# GPRSshield_V2.net
KiCad netlist of a schematic drawn in EAGLE
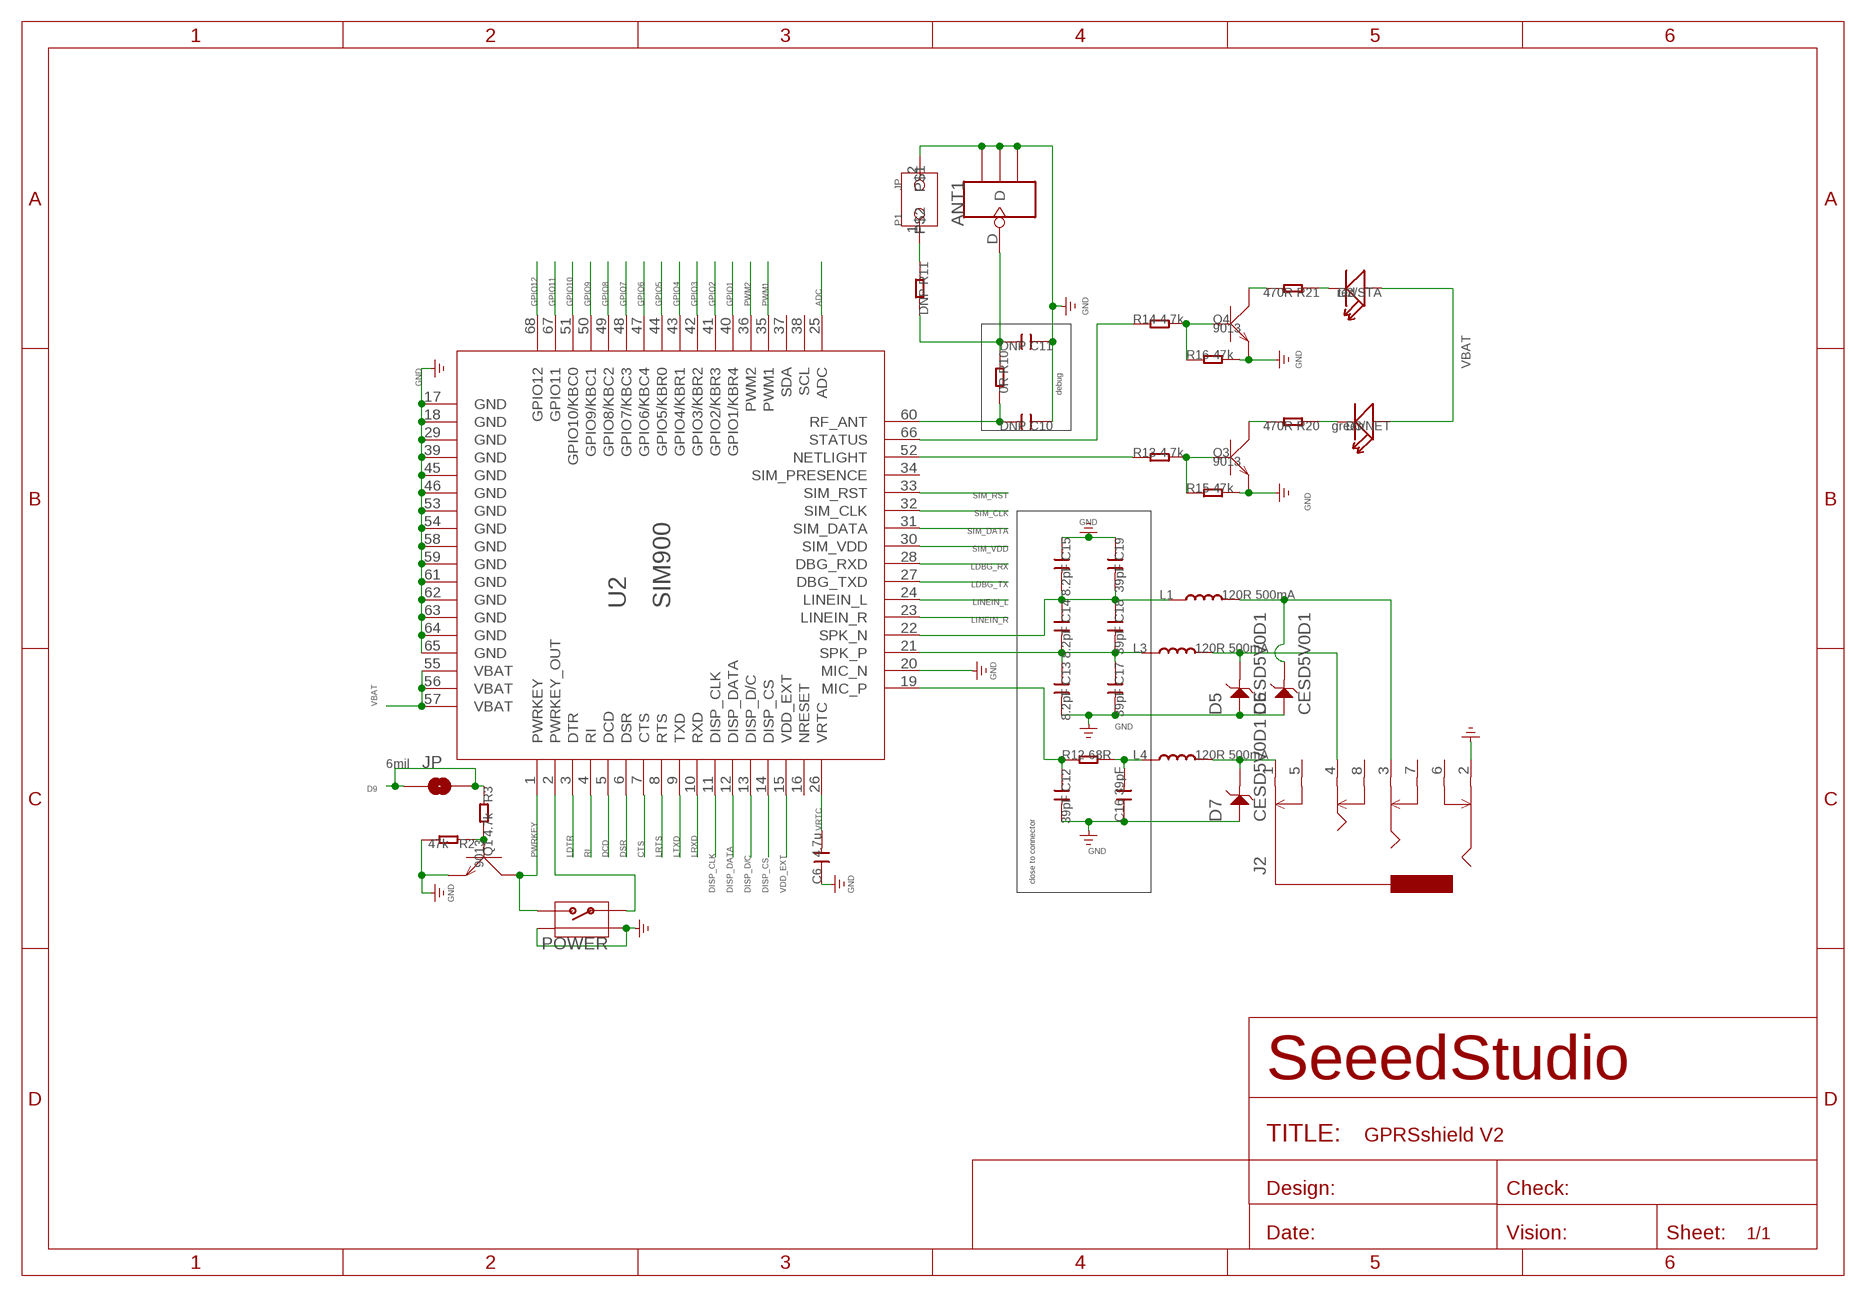
[diagram p0: schematic, sheet 1, part 1 of 2]
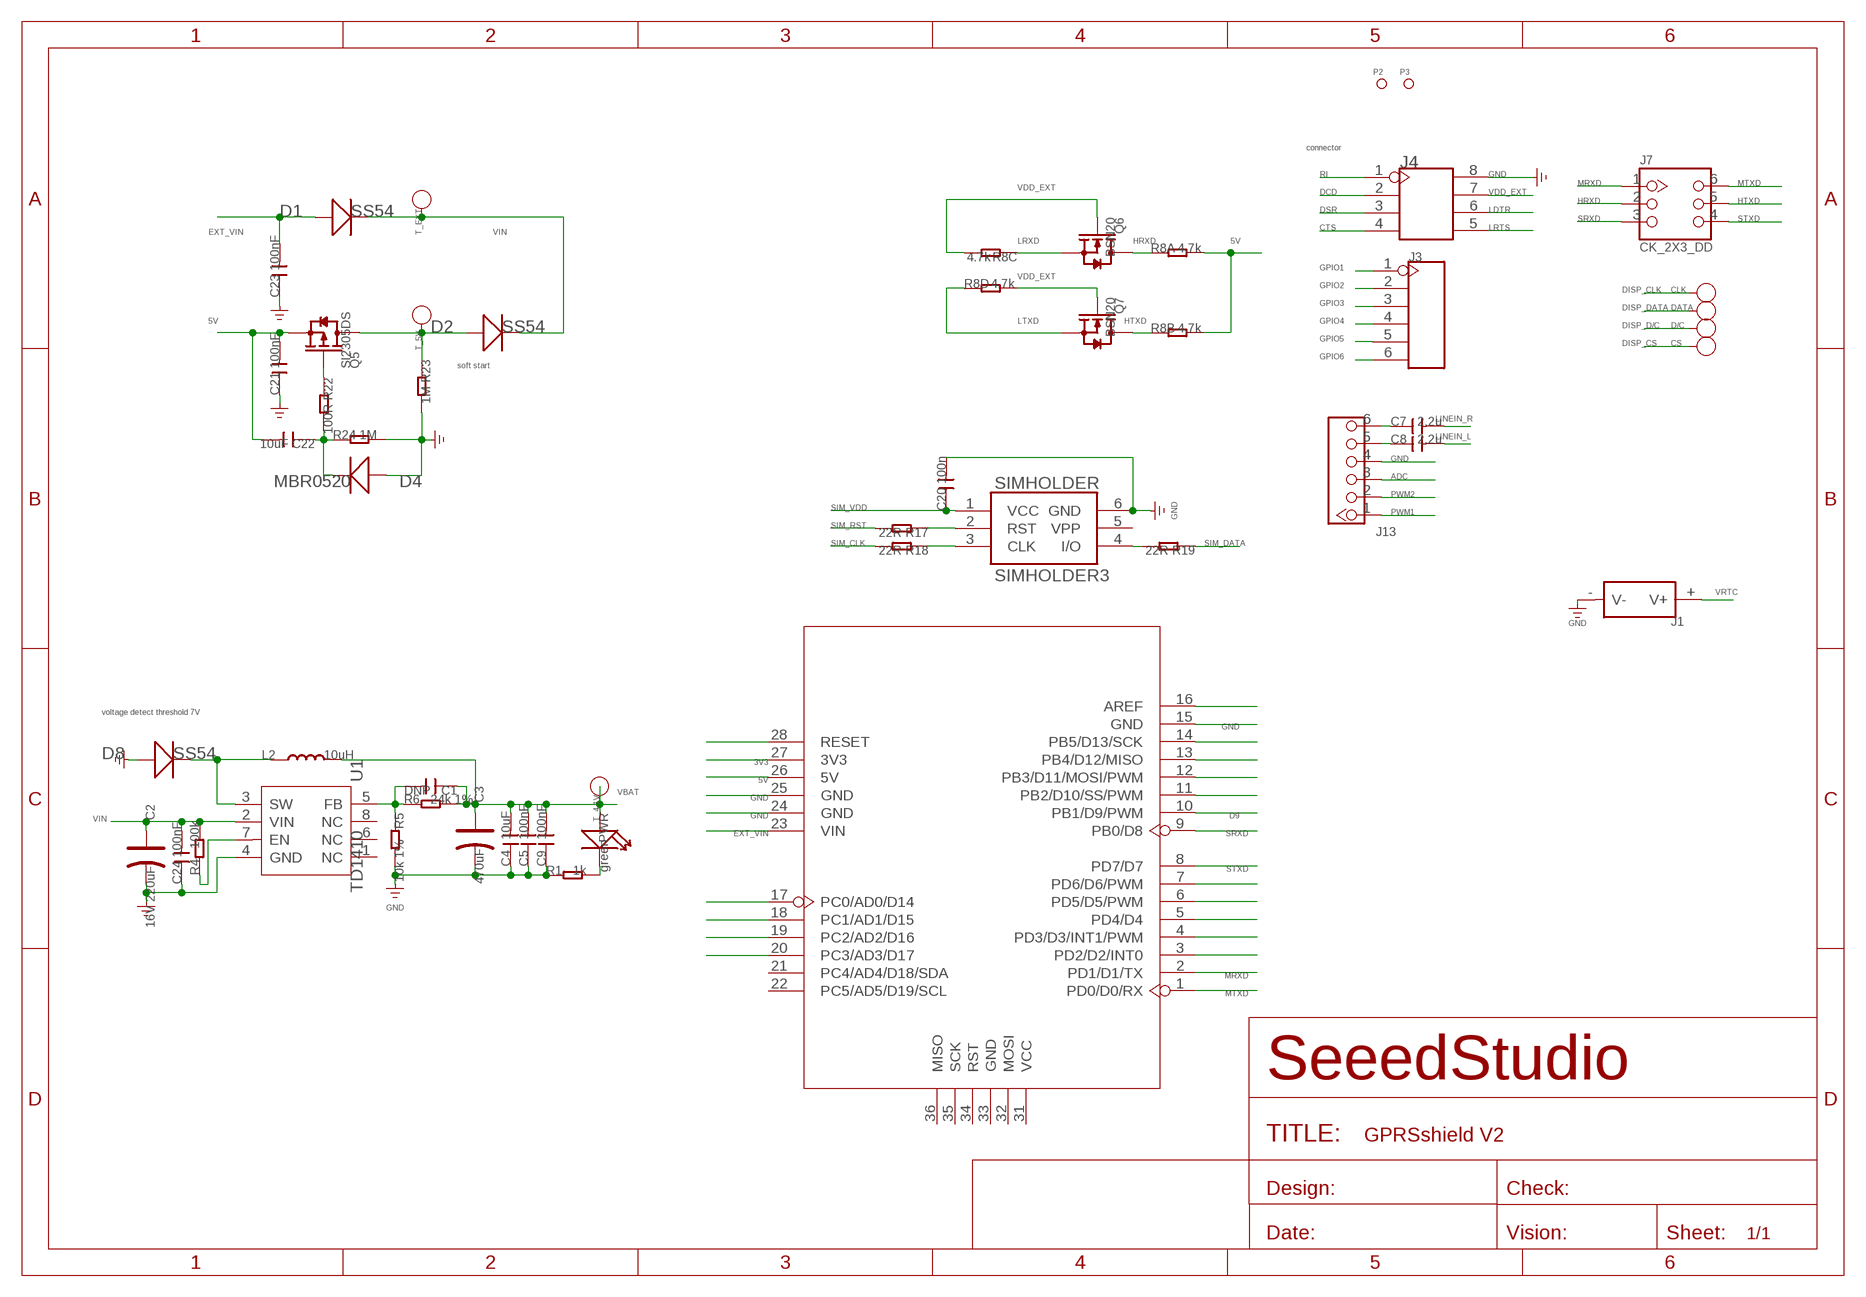
[diagram p1: schematic, sheet 1, part 2 of 2]

(export (version "E")
  (design (tool "Eeschema 10.0.6"))
  (components
    (comp (ref "ANT1")
      (value "ANTENNA-U-FL")
      (footprint "eagle-import:4P-U-FL")
      (libsource (lib "eagle-import") (part "ANTENNA-U-FL"))
    )
    (comp (ref "C1")
      (value "DNP")
      (footprint "eagle-import:C0603")
      (libsource (lib "eagle-import") (part "C-0603"))
    )
    (comp (ref "C2")
      (value "16V 220uF")
      (footprint "eagle-import:ELECTRO-SMD-D-5.6MM")
      (libsource (lib "eagle-import") (part "CAP-ELECTRO-D"))
    )
    (comp (ref "C3")
      (value "470uF")
      (footprint "eagle-import:AVX-D")
      (libsource (lib "eagle-import") (part "CAP-AVX-D"))
    )
    (comp (ref "C4")
      (value "10uF")
      (footprint "eagle-import:C0805")
      (libsource (lib "eagle-import") (part "C-0805"))
    )
    (comp (ref "C5")
      (value "100nF")
      (footprint "eagle-import:C0603")
      (libsource (lib "eagle-import") (part "C-0603"))
    )
    (comp (ref "C6")
      (value "4.7u")
      (footprint "eagle-import:C0805")
      (libsource (lib "eagle-import") (part "C-0805"))
    )
    (comp (ref "C7")
      (value "2.2u")
      (footprint "eagle-import:C0805")
      (libsource (lib "eagle-import") (part "C-0805"))
    )
    (comp (ref "C8")
      (value "2.2u")
      (footprint "eagle-import:C0805")
      (libsource (lib "eagle-import") (part "C-0805"))
    )
    (comp (ref "C9")
      (value "100nF")
      (footprint "eagle-import:C0603")
      (libsource (lib "eagle-import") (part "C-0603"))
    )
    (comp (ref "C10")
      (value "DNP")
      (footprint "eagle-import:C0603")
      (libsource (lib "eagle-import") (part "C-0603"))
    )
    (comp (ref "C11")
      (value "DNP")
      (footprint "eagle-import:C0603")
      (libsource (lib "eagle-import") (part "C-0603"))
    )
    (comp (ref "C12")
      (value "39pF")
      (footprint "eagle-import:C0603")
      (libsource (lib "eagle-import") (part "C-0603"))
    )
    (comp (ref "C13")
      (value "8.2pF")
      (footprint "eagle-import:C0603")
      (libsource (lib "eagle-import") (part "C-0603"))
    )
    (comp (ref "C14")
      (value "8.2pF")
      (footprint "eagle-import:C0603")
      (libsource (lib "eagle-import") (part "C-0603"))
    )
    (comp (ref "C15")
      (value "8.2pF")
      (footprint "eagle-import:C0603")
      (libsource (lib "eagle-import") (part "C-0603"))
    )
    (comp (ref "C16")
      (value "39pF")
      (footprint "eagle-import:C0603")
      (libsource (lib "eagle-import") (part "C-0603"))
    )
    (comp (ref "C17")
      (value "39pF")
      (footprint "eagle-import:C0603")
      (libsource (lib "eagle-import") (part "C-0603"))
    )
    (comp (ref "C18")
      (value "39pF")
      (footprint "eagle-import:C0603")
      (libsource (lib "eagle-import") (part "C-0603"))
    )
    (comp (ref "C19")
      (value "39pF")
      (footprint "eagle-import:C0603")
      (libsource (lib "eagle-import") (part "C-0603"))
    )
    (comp (ref "C20")
      (value "100n")
      (footprint "eagle-import:C0603")
      (libsource (lib "eagle-import") (part "C-0603"))
    )
    (comp (ref "C21")
      (value "100nF")
      (footprint "eagle-import:C0603")
      (libsource (lib "eagle-import") (part "C-0603"))
    )
    (comp (ref "C22")
      (value "10uF")
      (footprint "eagle-import:C0805")
      (libsource (lib "eagle-import") (part "C-0805"))
    )
    (comp (ref "C23")
      (value "100nF")
      (footprint "eagle-import:C0603")
      (libsource (lib "eagle-import") (part "C-0603"))
    )
    (comp (ref "C24")
      (value "100nF")
      (footprint "eagle-import:C0603")
      (libsource (lib "eagle-import") (part "C-0603"))
    )
    (comp (ref "CLK")
      (value "PAD-TEST-POINT-CIRCLE'4545'")
      (footprint "eagle-import:TP_4545")
      (fields (field (name "PARTNO") "DNP"))
      (libsource (lib "eagle-import") (part "PAD-TEST-POINT-CIRCLE'4545'"))
    )
    (comp (ref "CS")
      (value "PAD-TEST-POINT-CIRCLE'4545'")
      (footprint "eagle-import:TP_4545")
      (fields (field (name "PARTNO") "DNP"))
      (libsource (lib "eagle-import") (part "PAD-TEST-POINT-CIRCLE'4545'"))
    )
    (comp (ref "D/C")
      (value "PAD-TEST-POINT-CIRCLE'4545'")
      (footprint "eagle-import:TP_4545")
      (fields (field (name "PARTNO") "DNP"))
      (libsource (lib "eagle-import") (part "PAD-TEST-POINT-CIRCLE'4545'"))
    )
    (comp (ref "D1")
      (value "SS54")
      (footprint "eagle-import:SMB")
      (libsource (lib "eagle-import") (part "D'MBRS240LT3'"))
    )
    (comp (ref "D2")
      (value "SS54")
      (footprint "eagle-import:SMB")
      (libsource (lib "eagle-import") (part "D'MBRS240LT3'"))
    )
    (comp (ref "D2/STA")
      (value "red")
      (footprint "eagle-import:LED-0603")
      (libsource (lib "eagle-import") (part "LED'0603'"))
    )
    (comp (ref "D3/NET")
      (value "green")
      (footprint "eagle-import:LED-0603")
      (libsource (lib "eagle-import") (part "LED'0603'"))
    )
    (comp (ref "D4")
      (value "MBR0520")
      (footprint "eagle-import:SOD123-2.7X1.6")
      (libsource (lib "eagle-import") (part "D'MBR0520LT1'"))
    )
    (comp (ref "D5")
      (value "CESD5V0D1")
      (footprint "eagle-import:SOD123-2.7X1.6")
      (libsource (lib "eagle-import") (part "D-ESD"))
    )
    (comp (ref "D6")
      (value "CESD5V0D1")
      (footprint "eagle-import:SOD123-2.7X1.6")
      (libsource (lib "eagle-import") (part "D-ESD"))
    )
    (comp (ref "D7")
      (value "CESD5V0D1")
      (footprint "eagle-import:SOD123-2.7X1.6")
      (libsource (lib "eagle-import") (part "D-ESD"))
    )
    (comp (ref "D8")
      (value "SS54")
      (footprint "eagle-import:SMB")
      (libsource (lib "eagle-import") (part "D'MBRS240LT3'"))
    )
    (comp (ref "DATA")
      (value "PAD-TEST-POINT-CIRCLE'4545'")
      (footprint "eagle-import:TP_4545")
      (fields (field (name "PARTNO") "DNP"))
      (libsource (lib "eagle-import") (part "PAD-TEST-POINT-CIRCLE'4545'"))
    )
    (comp (ref "J1")
      (value "HOLDER-BAT")
      (footprint "eagle-import:SMD-CR1220-2")
      (libsource (lib "eagle-import") (part "HOLDER-BAT"))
    )
    (comp (ref "J2")
      (value "AUDIO-8P'PJ-3536-L6S'")
      (footprint "eagle-import:8P-3.5-SMD")
      (libsource (lib "eagle-import") (part "AUDIO-8P'PJ-3536-L6S'"))
    )
    (comp (ref "J3")
      (value "HEADER-6P-65/35MIL")
      (footprint "eagle-import:6P-2.54-65_35MIL")
      (libsource (lib "eagle-import") (part "HEADER-6P-65/35MIL"))
    )
    (comp (ref "J4")
      (value "HEADER-2X4P-2.54")
      (footprint "eagle-import:2X4P-2.54")
      (libsource (lib "eagle-import") (part "HEADER-2X4P-2.54"))
    )
    (comp (ref "J7")
      (value "CK_2X3_DD")
      (footprint "eagle-import:CK_2X3")
      (libsource (lib "eagle-import") (part "CK_2X3_DD"))
    )
    (comp (ref "J13")
      (value "HEADER_1X6")
      (footprint "eagle-import:CK_1X6")
      (libsource (lib "eagle-import") (part "HEADER_1X6"))
    )
    (comp (ref "JP")
      (value "PAD-SOLDERJUMPERNC")
      (footprint "eagle-import:2P-SMD-3.3X2")
      (libsource (lib "eagle-import") (part "PAD-SOLDERJUMPERNC"))
    )
    (comp (ref "L1")
      (value "120R 500mA")
      (footprint "eagle-import:L0603")
      (libsource (lib "eagle-import") (part "L'0603'"))
    )
    (comp (ref "L2")
      (value "10uH")
      (footprint "eagle-import:L0630")
      (libsource (lib "eagle-import") (part "L'0630'"))
    )
    (comp (ref "L3")
      (value "120R 500mA")
      (footprint "eagle-import:L0603")
      (libsource (lib "eagle-import") (part "L'0603'"))
    )
    (comp (ref "L4")
      (value "120R 500mA")
      (footprint "eagle-import:L0603")
      (libsource (lib "eagle-import") (part "L'0603'"))
    )
    (comp (ref "P1") (value "JP") (footprint "eagle-import:JP") (libsource (lib "eagle-import") (part "JP")))
    (comp (ref "P2")
      (value "PAD-MARK")
      (footprint "eagle-import:ROUND-MARK-1.0")
      (fields (field (name "PARTNO") "DNP"))
      (libsource (lib "eagle-import") (part "PAD-MARK"))
    )
    (comp (ref "P3")
      (value "PAD-MARK")
      (footprint "eagle-import:ROUND-MARK-1.0")
      (fields (field (name "PARTNO") "DNP"))
      (libsource (lib "eagle-import") (part "PAD-MARK"))
    )
    (comp (ref "POWER")
      (value "BUTTON-4P-REINFORCE'TS-118E'")
      (footprint "eagle-import:4P-SMD-7X3.5X3.5H")
      (libsource (lib "eagle-import") (part "BUTTON-4P-REINFORCE'TS-118E'"))
    )
    (comp (ref "PWR")
      (value "green")
      (footprint "eagle-import:D0603")
      (libsource (lib "eagle-import") (part "007-LED0603"))
    )
    (comp (ref "Q1")
      (value "9013")
      (footprint "eagle-import:SOT23")
      (libsource (lib "eagle-import") (part "TRANSISTOR-NPN-SOT23"))
    )
    (comp (ref "Q3")
      (value "9013")
      (footprint "eagle-import:SOT23")
      (libsource (lib "eagle-import") (part "TRANSISTOR-NPN-SOT23"))
    )
    (comp (ref "Q4")
      (value "9013")
      (footprint "eagle-import:SOT23")
      (libsource (lib "eagle-import") (part "TRANSISTOR-NPN-SOT23"))
    )
    (comp (ref "Q5")
      (value "SI2305DS")
      (footprint "eagle-import:SOT23")
      (libsource (lib "eagle-import") (part "MOSFET-P'SI2323CDS/SI2305DS{lt}BR{gt}'"))
    )
    (comp (ref "Q6")
      (value "BSN20")
      (footprint "eagle-import:SOT23")
      (libsource (lib "eagle-import") (part "MOSFET-N'SOT23'"))
    )
    (comp (ref "Q7")
      (value "BSN20")
      (footprint "eagle-import:SOT23")
      (libsource (lib "eagle-import") (part "MOSFET-N'SOT23'"))
    )
    (comp (ref "R1")
      (value "1k")
      (footprint "eagle-import:R0603")
      (libsource (lib "eagle-import") (part "R-0603"))
    )
    (comp (ref "R2")
      (value "47k")
      (footprint "eagle-import:R0603")
      (libsource (lib "eagle-import") (part "R-0603"))
    )
    (comp (ref "R3")
      (value "4.7k")
      (footprint "eagle-import:R0603")
      (libsource (lib "eagle-import") (part "R-0603"))
    )
    (comp (ref "R4")
      (value "100k")
      (footprint "eagle-import:R0603")
      (libsource (lib "eagle-import") (part "R-0603"))
    )
    (comp (ref "R5")
      (value "10k 1%")
      (footprint "eagle-import:R0603")
      (libsource (lib "eagle-import") (part "R-0603"))
    )
    (comp (ref "R6")
      (value "24k 1%")
      (footprint "eagle-import:R0603")
      (libsource (lib "eagle-import") (part "R-0603"))
    )
    (comp (ref "R8")
      (value "4.7k")
      (footprint "eagle-import:1206-8-3.3X2.4")
      (libsource (lib "eagle-import") (part "R-4R-1206"))
    )
    (comp (ref "R10")
      (value "0R")
      (footprint "eagle-import:R0603")
      (libsource (lib "eagle-import") (part "R-0603"))
    )
    (comp (ref "R11")
      (value "DNP")
      (footprint "eagle-import:R0603")
      (libsource (lib "eagle-import") (part "R-0603"))
    )
    (comp (ref "R12")
      (value "68R")
      (footprint "eagle-import:R0603")
      (libsource (lib "eagle-import") (part "R-0603"))
    )
    (comp (ref "R13")
      (value "4.7k")
      (footprint "eagle-import:R0603")
      (libsource (lib "eagle-import") (part "R-0603"))
    )
    (comp (ref "R14")
      (value "4.7k")
      (footprint "eagle-import:R0603")
      (libsource (lib "eagle-import") (part "R-0603"))
    )
    (comp (ref "R15")
      (value "47k")
      (footprint "eagle-import:R0603")
      (libsource (lib "eagle-import") (part "R-0603"))
    )
    (comp (ref "R16")
      (value "47k")
      (footprint "eagle-import:R0603")
      (libsource (lib "eagle-import") (part "R-0603"))
    )
    (comp (ref "R17")
      (value "22R")
      (footprint "eagle-import:R0603")
      (libsource (lib "eagle-import") (part "R-0603"))
    )
    (comp (ref "R18")
      (value "22R")
      (footprint "eagle-import:R0603")
      (libsource (lib "eagle-import") (part "R-0603"))
    )
    (comp (ref "R19")
      (value "22R")
      (footprint "eagle-import:R0603")
      (libsource (lib "eagle-import") (part "R-0603"))
    )
    (comp (ref "R20")
      (value "470R")
      (footprint "eagle-import:R0603")
      (libsource (lib "eagle-import") (part "R-0603"))
    )
    (comp (ref "R21")
      (value "470R")
      (footprint "eagle-import:R0603")
      (libsource (lib "eagle-import") (part "R-0603"))
    )
    (comp (ref "R22")
      (value "100R")
      (footprint "eagle-import:R0603")
      (libsource (lib "eagle-import") (part "R-0603"))
    )
    (comp (ref "R23")
      (value "1M")
      (footprint "eagle-import:R0603")
      (libsource (lib "eagle-import") (part "R-0603"))
    )
    (comp (ref "R24")
      (value "1M")
      (footprint "eagle-import:R0603")
      (libsource (lib "eagle-import") (part "R-0603"))
    )
    (comp (ref "SIMHOLDER")
      (value "SIMHOLDER3")
      (footprint "eagle-import:SIMHOLDER3")
      (libsource (lib "eagle-import") (part "SIMHOLDER3"))
    )
    (comp (ref "T_4.1V")
      (value "PAD-TEST-POINT-CIRCLE'4545'")
      (footprint "eagle-import:TP_4545")
      (fields (field (name "PARTNO") "DNP") (field (name "PARTNO_1") "DNP"))
      (libsource (lib "eagle-import") (part "PAD-TEST-POINT-CIRCLE'4545'"))
    )
    (comp (ref "T_5V")
      (value "PAD-TEST-POINT-CIRCLE'4545'")
      (footprint "eagle-import:TP_4545")
      (fields (field (name "PARTNO") "DNP") (field (name "PARTNO_1") "DNP"))
      (libsource (lib "eagle-import") (part "PAD-TEST-POINT-CIRCLE'4545'"))
    )
    (comp (ref "T_EXT")
      (value "PAD-TEST-POINT-CIRCLE'4545'")
      (footprint "eagle-import:TP_4545")
      (fields (field (name "PARTNO") "DNP") (field (name "PARTNO_1") "DNP"))
      (libsource (lib "eagle-import") (part "PAD-TEST-POINT-CIRCLE'4545'"))
    )
    (comp (ref "U1")
      (value "TD1410")
      (footprint "eagle-import:SOP8")
      (libsource (lib "eagle-import") (part "TD1410"))
    )
    (comp (ref "U2")
      (value "SIM900")
      (footprint "eagle-import:SIM900")
      (libsource (lib "eagle-import") (part "SIM900"))
    )
    (comp (ref "U3")
      (value "ARDUINO'W/O-SILK'")
      (footprint "eagle-import:ARDUINO-W_O-SILK")
      (libsource (lib "eagle-import") (part "ARDUINO'W/O-SILK'"))
    )
  )
  (nets
    (net (code "1") (name "/3V3") (class "Default")
      (node (ref "U3") (pin "27") (pinfunction "3V3_27") (pintype "bidirectional"))
    )
    (net (code "2") (name "/5V") (class "Default")
      (node (ref "C21") (pin "2") (pinfunction "2_2") (pintype "passive"))
      (node (ref "C22") (pin "2") (pinfunction "2_2") (pintype "passive"))
      (node (ref "Q5") (pin "2") (pinfunction "S_2") (pintype "passive"))
      (node (ref "R8") (pin "7") (pinfunction "2_7") (pintype "passive"))
      (node (ref "R8") (pin "8") (pinfunction "2_8") (pintype "passive"))
      (node (ref "U3") (pin "26") (pinfunction "5V_26") (pintype "bidirectional"))
    )
    (net (code "3") (name "/ADC") (class "Default")
      (node (ref "J13") (pin "3") (pinfunction "3_3") (pintype "bidirectional"))
      (node (ref "U2") (pin "25") (pinfunction "ADC_25") (pintype "input"))
    )
    (net (code "4") (name "/CTS") (class "Default")
      (node (ref "J4") (pin "4") (pinfunction "4_4") (pintype "bidirectional"))
      (node (ref "U2") (pin "7") (pinfunction "CTS_7") (pintype "output"))
    )
    (net (code "5") (name "/D9") (class "Default")
      (node (ref "JP") (pin "1") (pinfunction "1_1") (pintype "passive"))
      (node (ref "JP") (pin "2") (pinfunction "2_2") (pintype "passive"))
      (node (ref "R3") (pin "1") (pinfunction "1_1") (pintype "passive"))
      (node (ref "U3") (pin "10") (pinfunction "PB1/D9/PWM_10") (pintype "bidirectional"))
    )
    (net (code "6") (name "/DCD") (class "Default")
      (node (ref "J4") (pin "2") (pinfunction "2_2") (pintype "bidirectional"))
      (node (ref "U2") (pin "5") (pinfunction "DCD_5") (pintype "output"))
    )
    (net (code "7") (name "/DISP_CLK") (class "Default")
      (node (ref "CLK") (pin "T") (pinfunction "T_T") (pintype "bidirectional"))
      (node (ref "U2") (pin "11") (pinfunction "DISP_CLK_11") (pintype "output"))
    )
    (net (code "8") (name "/DISP_CS") (class "Default")
      (node (ref "CS") (pin "T") (pinfunction "T_T") (pintype "bidirectional"))
      (node (ref "U2") (pin "14") (pinfunction "DISP_CS_14") (pintype "output"))
    )
    (net (code "9") (name "/DISP_DATA") (class "Default")
      (node (ref "DATA") (pin "T") (pinfunction "T_T") (pintype "bidirectional"))
      (node (ref "U2") (pin "12") (pinfunction "DISP_DATA_12") (pintype "bidirectional"))
    )
    (net (code "10") (name "/DISP_D{slash}C") (class "Default")
      (node (ref "D/C") (pin "T") (pinfunction "T_T") (pintype "bidirectional"))
      (node (ref "U2") (pin "13") (pinfunction "DISP_D/C_13") (pintype "output"))
    )
    (net (code "11") (name "/DSR") (class "Default")
      (node (ref "J4") (pin "3") (pinfunction "3_3") (pintype "bidirectional"))
      (node (ref "U2") (pin "6") (pinfunction "DSR_6") (pintype "output"))
    )
    (net (code "12") (name "/EXT_VIN") (class "Default")
      (node (ref "C23") (pin "2") (pinfunction "2_2") (pintype "passive"))
      (node (ref "D1") (pin "+") (pinfunction "+_+") (pintype "passive"))
      (node (ref "U3") (pin "23") (pinfunction "VIN_23") (pintype "bidirectional"))
    )
    (net (code "13") (name "/GPIO1") (class "Default")
      (node (ref "J3") (pin "1") (pinfunction "1_1") (pintype "bidirectional"))
      (node (ref "U2") (pin "40") (pinfunction "GPIO1/KBR4_40") (pintype "output"))
    )
    (net (code "14") (name "/GPIO2") (class "Default")
      (node (ref "J3") (pin "2") (pinfunction "2_2") (pintype "bidirectional"))
      (node (ref "U2") (pin "41") (pinfunction "GPIO2/KBR3_41") (pintype "output"))
    )
    (net (code "15") (name "/GPIO3") (class "Default")
      (node (ref "J3") (pin "3") (pinfunction "3_3") (pintype "bidirectional"))
      (node (ref "U2") (pin "42") (pinfunction "GPIO3/KBR2_42") (pintype "output"))
    )
    (net (code "16") (name "/GPIO4") (class "Default")
      (node (ref "J3") (pin "4") (pinfunction "4_4") (pintype "bidirectional"))
      (node (ref "U2") (pin "43") (pinfunction "GPIO4/KBR1_43") (pintype "output"))
    )
    (net (code "17") (name "/GPIO5") (class "Default")
      (node (ref "J3") (pin "5") (pinfunction "5_5") (pintype "bidirectional"))
      (node (ref "U2") (pin "44") (pinfunction "GPIO5/KBR0_44") (pintype "output"))
    )
    (net (code "18") (name "/GPIO6") (class "Default")
      (node (ref "J3") (pin "6") (pinfunction "6_6") (pintype "bidirectional"))
      (node (ref "U2") (pin "47") (pinfunction "GPIO6/KBC4_47") (pintype "input"))
    )
    (net (code "19") (name "/GPIO7") (class "Default")
      (node (ref "U2") (pin "48") (pinfunction "GPIO7/KBC3_48") (pintype "bidirectional"))
    )
    (net (code "20") (name "/GPIO8") (class "Default")
      (node (ref "U2") (pin "49") (pinfunction "GPIO8/KBC2_49") (pintype "input"))
    )
    (net (code "21") (name "/GPIO9") (class "Default")
      (node (ref "U2") (pin "50") (pinfunction "GPIO9/KBC1_50") (pintype "input"))
    )
    (net (code "22") (name "/GPIO10") (class "Default")
      (node (ref "U2") (pin "51") (pinfunction "GPIO10/KBC0_51") (pintype "bidirectional"))
    )
    (net (code "23") (name "/GPIO11") (class "Default")
      (node (ref "U2") (pin "67") (pinfunction "GPIO11_67") (pintype "bidirectional"))
    )
    (net (code "24") (name "/GPIO12") (class "Default")
      (node (ref "U2") (pin "68") (pinfunction "GPIO12_68") (pintype "bidirectional"))
    )
    (net (code "25") (name "/HRXD") (class "Default")
      (node (ref "J7") (pin "2") (pinfunction "2_2") (pintype "bidirectional"))
      (node (ref "Q6") (pin "3") (pinfunction "D_3") (pintype "passive"))
      (node (ref "R8") (pin "1") (pinfunction "1_1") (pintype "passive"))
    )
    (net (code "26") (name "/HTXD") (class "Default")
      (node (ref "J7") (pin "5") (pinfunction "5_5") (pintype "bidirectional"))
      (node (ref "Q7") (pin "3") (pinfunction "D_3") (pintype "passive"))
      (node (ref "R8") (pin "2") (pinfunction "1_2") (pintype "passive"))
    )
    (net (code "27") (name "/LDBG_RX") (class "Default")
      (node (ref "U2") (pin "28") (pinfunction "DBG_RXD_28") (pintype "input"))
    )
    (net (code "28") (name "/LDBG_TX") (class "Default")
      (node (ref "U2") (pin "27") (pinfunction "DBG_TXD_27") (pintype "output"))
    )
    (net (code "29") (name "/LDTR") (class "Default")
      (node (ref "J4") (pin "6") (pinfunction "6_6") (pintype "bidirectional"))
      (node (ref "U2") (pin "3") (pinfunction "DTR_3") (pintype "input"))
    )
    (net (code "30") (name "/LINEIN_L") (class "Default")
      (node (ref "C8") (pin "2") (pinfunction "2_2") (pintype "passive"))
      (node (ref "U2") (pin "24") (pinfunction "LINEIN_L_24") (pintype "input"))
    )
    (net (code "31") (name "/LINEIN_R") (class "Default")
      (node (ref "C7") (pin "2") (pinfunction "2_2") (pintype "passive"))
      (node (ref "U2") (pin "23") (pinfunction "LINEIN_R_23") (pintype "input"))
    )
    (net (code "32") (name "/LRTS") (class "Default")
      (node (ref "J4") (pin "5") (pinfunction "5_5") (pintype "bidirectional"))
      (node (ref "U2") (pin "8") (pinfunction "RTS_8") (pintype "input"))
    )
    (net (code "33") (name "/LRXD") (class "Default")
      (node (ref "Q6") (pin "2") (pinfunction "S_2") (pintype "passive"))
      (node (ref "R8") (pin "3") (pinfunction "1_3") (pintype "passive"))
      (node (ref "U2") (pin "10") (pinfunction "RXD_10") (pintype "input"))
    )
    (net (code "34") (name "/LTXD") (class "Default")
      (node (ref "Q7") (pin "2") (pinfunction "S_2") (pintype "passive"))
      (node (ref "R8") (pin "4") (pinfunction "1_4") (pintype "passive"))
      (node (ref "U2") (pin "9") (pinfunction "TXD_9") (pintype "output"))
    )
    (net (code "35") (name "/MRXD") (class "Default")
      (node (ref "J7") (pin "1") (pinfunction "1_1") (pintype "bidirectional"))
      (node (ref "U3") (pin "2") (pinfunction "PD1/D1/TX_2") (pintype "bidirectional"))
    )
    (net (code "36") (name "/MTXD") (class "Default")
      (node (ref "J7") (pin "6") (pinfunction "6_6") (pintype "bidirectional"))
      (node (ref "U3") (pin "1") (pinfunction "PD0/D0/RX_1") (pintype "bidirectional"))
    )
    (net (code "37") (name "/PWM1") (class "Default")
      (node (ref "J13") (pin "1") (pinfunction "1_1") (pintype "bidirectional"))
      (node (ref "U2") (pin "35") (pinfunction "PWM1_35") (pintype "output"))
    )
    (net (code "38") (name "/PWM2") (class "Default")
      (node (ref "J13") (pin "2") (pinfunction "2_2") (pintype "bidirectional"))
      (node (ref "U2") (pin "36") (pinfunction "PWM2_36") (pintype "output"))
    )
    (net (code "39") (name "/PWRKEY") (class "Default")
      (node (ref "POWER") (pin "2") (pinfunction "2_2") (pintype "bidirectional"))
      (node (ref "Q1") (pin "3") (pinfunction "C_3") (pintype "passive"))
      (node (ref "U2") (pin "1") (pinfunction "PWRKEY_1") (pintype "input"))
    )
    (net (code "40") (name "/RI") (class "Default")
      (node (ref "J4") (pin "1") (pinfunction "1_1") (pintype "bidirectional"))
      (node (ref "U2") (pin "4") (pinfunction "RI_4") (pintype "output"))
    )
    (net (code "41") (name "/SIM_CLK") (class "Default")
      (node (ref "R18") (pin "2") (pinfunction "2_2") (pintype "passive"))
      (node (ref "U2") (pin "32") (pinfunction "SIM_CLK_32") (pintype "output"))
    )
    (net (code "42") (name "/SIM_DATA") (class "Default")
      (node (ref "R19") (pin "1") (pinfunction "1_1") (pintype "passive"))
      (node (ref "U2") (pin "31") (pinfunction "SIM_DATA_31") (pintype "bidirectional"))
    )
    (net (code "43") (name "/SIM_RST") (class "Default")
      (node (ref "R17") (pin "2") (pinfunction "2_2") (pintype "passive"))
      (node (ref "U2") (pin "33") (pinfunction "SIM_RST_33") (pintype "output"))
    )
    (net (code "44") (name "/SIM_VDD") (class "Default")
      (node (ref "C20") (pin "1") (pinfunction "1_1") (pintype "passive"))
      (node (ref "SIMHOLDER") (pin "1") (pinfunction "VCC_1") (pintype "bidirectional"))
      (node (ref "U2") (pin "30") (pinfunction "SIM_VDD_30") (pintype "output"))
    )
    (net (code "45") (name "/SRXD") (class "Default")
      (node (ref "J7") (pin "3") (pinfunction "3_3") (pintype "bidirectional"))
      (node (ref "U3") (pin "9") (pinfunction "PB0/D8_9") (pintype "bidirectional"))
    )
    (net (code "46") (name "/STXD") (class "Default")
      (node (ref "J7") (pin "4") (pinfunction "4_4") (pintype "bidirectional"))
      (node (ref "U3") (pin "8") (pinfunction "PD7/D7_8") (pintype "bidirectional"))
    )
    (net (code "47") (name "/VBAT") (class "Default")
      (node (ref "C1") (pin "1") (pinfunction "1_1") (pintype "passive"))
      (node (ref "C3") (pin "+") (pinfunction "+_+") (pintype "passive"))
      (node (ref "C4") (pin "2") (pinfunction "2_2") (pintype "passive"))
      (node (ref "C5") (pin "2") (pinfunction "2_2") (pintype "passive"))
      (node (ref "C9") (pin "2") (pinfunction "2_2") (pintype "passive"))
      (node (ref "D2/STA") (pin "+") (pinfunction "+_+") (pintype "passive"))
      (node (ref "D3/NET") (pin "+") (pinfunction "+_+") (pintype "passive"))
      (node (ref "L2") (pin "2") (pinfunction "2_2") (pintype "passive"))
      (node (ref "PWR") (pin "+") (pinfunction "+_+") (pintype "passive"))
      (node (ref "R6") (pin "2") (pinfunction "2_2") (pintype "passive"))
      (node (ref "T_4.1V") (pin "T") (pinfunction "T_T") (pintype "bidirectional"))
      (node (ref "U2") (pin "55") (pinfunction "VBAT_55") (pintype "power_in"))
      (node (ref "U2") (pin "56") (pinfunction "VBAT_56") (pintype "power_in"))
      (node (ref "U2") (pin "57") (pinfunction "VBAT_57") (pintype "power_in"))
    )
    (net (code "48") (name "/VDD_EXT") (class "Default")
      (node (ref "J4") (pin "7") (pinfunction "7_7") (pintype "bidirectional"))
      (node (ref "Q6") (pin "1") (pinfunction "G_1") (pintype "passive"))
      (node (ref "Q7") (pin "1") (pinfunction "G_1") (pintype "passive"))
      (node (ref "R8") (pin "5") (pinfunction "2_5") (pintype "passive"))
      (node (ref "R8") (pin "6") (pinfunction "2_6") (pintype "passive"))
      (node (ref "U2") (pin "15") (pinfunction "VDD_EXT_15") (pintype "output"))
    )
    (net (code "49") (name "/VIN") (class "Default")
      (node (ref "C2") (pin "+") (pinfunction "+_+") (pintype "passive"))
      (node (ref "C24") (pin "2") (pinfunction "2_2") (pintype "passive"))
      (node (ref "D1") (pin "-") (pinfunction "-_-") (pintype "passive"))
      (node (ref "D2") (pin "-") (pinfunction "-_-") (pintype "passive"))
      (node (ref "R4") (pin "2") (pinfunction "2_2") (pintype "passive"))
      (node (ref "T_EXT") (pin "T") (pinfunction "T_T") (pintype "bidirectional"))
      (node (ref "U1") (pin "2") (pinfunction "VIN_2") (pintype "input"))
    )
    (net (code "50") (name "/VRTC") (class "Default")
      (node (ref "C6") (pin "2") (pinfunction "2_2") (pintype "passive"))
      (node (ref "J1") (pin "+") (pinfunction "V+_+") (pintype "bidirectional"))
      (node (ref "U2") (pin "26") (pinfunction "VRTC_26") (pintype "bidirectional"))
    )
    (net (code "51") (name "GND_POWER") (class "Default")
      (node (ref "ANT1") (pin "GND1") (pinfunction "GND1_GND1") (pintype "bidirectional"))
      (node (ref "ANT1") (pin "GND2") (pinfunction "GND2_GND2") (pintype "bidirectional"))
      (node (ref "ANT1") (pin "GND3") (pinfunction "GND3_GND3") (pintype "bidirectional"))
      (node (ref "C10") (pin "1") (pinfunction "1_1") (pintype "passive"))
      (node (ref "C11") (pin "1") (pinfunction "1_1") (pintype "passive"))
      (node (ref "C12") (pin "2") (pinfunction "2_2") (pintype "passive"))
      (node (ref "C13") (pin "2") (pinfunction "2_2") (pintype "passive"))
      (node (ref "C15") (pin "1") (pinfunction "1_1") (pintype "passive"))
      (node (ref "C16") (pin "1") (pinfunction "1_1") (pintype "passive"))
      (node (ref "C17") (pin "2") (pinfunction "2_2") (pintype "passive"))
      (node (ref "C19") (pin "1") (pinfunction "1_1") (pintype "passive"))
      (node (ref "C2") (pin "-") (pinfunction "-_-") (pintype "passive"))
      (node (ref "C20") (pin "2") (pinfunction "2_2") (pintype "passive"))
      (node (ref "C21") (pin "1") (pinfunction "1_1") (pintype "passive"))
      (node (ref "C23") (pin "1") (pinfunction "1_1") (pintype "passive"))
      (node (ref "C24") (pin "1") (pinfunction "1_1") (pintype "passive"))
      (node (ref "C3") (pin "-") (pinfunction "-_-") (pintype "passive"))
      (node (ref "C4") (pin "1") (pinfunction "1_1") (pintype "passive"))
      (node (ref "C5") (pin "1") (pinfunction "1_1") (pintype "passive"))
      (node (ref "C6") (pin "1") (pinfunction "1_1") (pintype "passive"))
      (node (ref "C9") (pin "1") (pinfunction "1_1") (pintype "passive"))
      (node (ref "D4") (pin "1") (pinfunction "+_1") (pintype "passive"))
      (node (ref "D5") (pin "1") (pinfunction "1_1") (pintype "bidirectional"))
      (node (ref "D6") (pin "1") (pinfunction "1_1") (pintype "bidirectional"))
      (node (ref "D7") (pin "1") (pinfunction "1_1") (pintype "bidirectional"))
      (node (ref "D8") (pin "+") (pinfunction "+_+") (pintype "passive"))
      (node (ref "J1") (pin "-") (pinfunction "V-_-") (pintype "bidirectional"))
      (node (ref "J13") (pin "4") (pinfunction "4_4") (pintype "bidirectional"))
      (node (ref "J2") (pin "2") (pinfunction "2_2") (pintype "bidirectional"))
      (node (ref "J4") (pin "8") (pinfunction "8_8") (pintype "bidirectional"))
      (node (ref "P1") (pin "2") (pinfunction "P$2_2") (pintype "bidirectional"))
      (node (ref "POWER") (pin "S1") (pinfunction "S1_S1") (pintype "bidirectional"))
      (node (ref "POWER") (pin "S2") (pinfunction "S2_S2") (pintype "bidirectional"))
      (node (ref "Q1") (pin "2") (pinfunction "E_2") (pintype "passive"))
      (node (ref "Q3") (pin "2") (pinfunction "E_2") (pintype "passive"))
      (node (ref "Q4") (pin "2") (pinfunction "E_2") (pintype "passive"))
      (node (ref "R1") (pin "1") (pinfunction "1_1") (pintype "passive"))
      (node (ref "R15") (pin "2") (pinfunction "2_2") (pintype "passive"))
      (node (ref "R16") (pin "2") (pinfunction "2_2") (pintype "passive"))
      (node (ref "R2") (pin "2") (pinfunction "2_2") (pintype "passive"))
      (node (ref "R23") (pin "2") (pinfunction "2_2") (pintype "passive"))
      (node (ref "R24") (pin "2") (pinfunction "2_2") (pintype "passive"))
      (node (ref "R5") (pin "2") (pinfunction "2_2") (pintype "passive"))
      (node (ref "SIMHOLDER") (pin "6") (pinfunction "GND_6") (pintype "bidirectional"))
      (node (ref "U1") (pin "4") (pinfunction "GND_4") (pintype "power_in"))
      (node (ref "U2") (pin "17") (pinfunction "GND_17") (pintype "power_in"))
      (node (ref "U2") (pin "18") (pinfunction "GND_18") (pintype "power_in"))
      (node (ref "U2") (pin "20") (pinfunction "MIC_N_20") (pintype "input"))
      (node (ref "U2") (pin "29") (pinfunction "GND_29") (pintype "power_in"))
      (node (ref "U2") (pin "39") (pinfunction "GND_39") (pintype "power_in"))
      (node (ref "U2") (pin "45") (pinfunction "GND_45") (pintype "power_in"))
      (node (ref "U2") (pin "46") (pinfunction "GND_46") (pintype "power_in"))
      (node (ref "U2") (pin "53") (pinfunction "GND_53") (pintype "power_in"))
      (node (ref "U2") (pin "54") (pinfunction "GND_54") (pintype "power_in"))
      (node (ref "U2") (pin "58") (pinfunction "GND_58") (pintype "power_in"))
      (node (ref "U2") (pin "59") (pinfunction "GND_59") (pintype "power_in"))
      (node (ref "U2") (pin "61") (pinfunction "GND_61") (pintype "power_in"))
      (node (ref "U2") (pin "62") (pinfunction "GND_62") (pintype "power_in"))
      (node (ref "U2") (pin "63") (pinfunction "GND_63") (pintype "power_in"))
      (node (ref "U2") (pin "64") (pinfunction "GND_64") (pintype "power_in"))
      (node (ref "U2") (pin "65") (pinfunction "GND_65") (pintype "power_in"))
      (node (ref "U3") (pin "15") (pinfunction "GND_15") (pintype "bidirectional"))
      (node (ref "U3") (pin "24") (pinfunction "GND_24") (pintype "bidirectional"))
      (node (ref "U3") (pin "25") (pinfunction "GND_25") (pintype "bidirectional"))
    )
    (net (code "52") (name "Net-(ANT1-PadD)") (class "Default")
      (node (ref "ANT1") (pin "D") (pinfunction "D_D") (pintype "bidirectional"))
      (node (ref "C11") (pin "2") (pinfunction "2_2") (pintype "passive"))
      (node (ref "R10") (pin "1") (pinfunction "1_1") (pintype "passive"))
      (node (ref "R11") (pin "2") (pinfunction "2_2") (pintype "passive"))
    )
    (net (code "53") (name "Net-(C7-Pad1)") (class "Default")
      (node (ref "C7") (pin "1") (pinfunction "1_1") (pintype "passive"))
      (node (ref "J13") (pin "6") (pinfunction "6_6") (pintype "bidirectional"))
    )
    (net (code "54") (name "Net-(C8-Pad1)") (class "Default")
      (node (ref "C8") (pin "1") (pinfunction "1_1") (pintype "passive"))
      (node (ref "J13") (pin "5") (pinfunction "5_5") (pintype "bidirectional"))
    )
    (net (code "55") (name "Net-(C16-Pad2)") (class "Default")
      (node (ref "C16") (pin "2") (pinfunction "2_2") (pintype "passive"))
      (node (ref "L4") (pin "1") (pinfunction "1_1") (pintype "passive"))
      (node (ref "R12") (pin "2") (pinfunction "2_2") (pintype "passive"))
    )
    (net (code "56") (name "Net-(D2/STA-Pad-)") (class "Default")
      (node (ref "D2/STA") (pin "-") (pinfunction "-_-") (pintype "passive"))
      (node (ref "R21") (pin "1") (pinfunction "1_1") (pintype "passive"))
    )
    (net (code "57") (name "Net-(D3/NET-Pad-)") (class "Default")
      (node (ref "D3/NET") (pin "-") (pinfunction "-_-") (pintype "passive"))
      (node (ref "R20") (pin "1") (pinfunction "1_1") (pintype "passive"))
    )
    (net (code "58") (name "Net-(D4--)") (class "Default")
      (node (ref "C22") (pin "1") (pinfunction "1_1") (pintype "passive"))
      (node (ref "D4") (pin "2") (pinfunction "-_2") (pintype "passive"))
      (node (ref "R22") (pin "2") (pinfunction "2_2") (pintype "passive"))
      (node (ref "R24") (pin "1") (pinfunction "1_1") (pintype "passive"))
    )
    (net (code "59") (name "Net-(D5-Pad2)") (class "Default")
      (node (ref "D5") (pin "2") (pinfunction "2_2") (pintype "bidirectional"))
      (node (ref "J2") (pin "4") (pinfunction "4_4") (pintype "bidirectional"))
      (node (ref "L3") (pin "2") (pinfunction "2_2") (pintype "passive"))
    )
    (net (code "60") (name "Net-(D6-Pad2)") (class "Default")
      (node (ref "D6") (pin "2") (pinfunction "2_2") (pintype "bidirectional"))
      (node (ref "J2") (pin "3") (pinfunction "3_3") (pintype "bidirectional"))
      (node (ref "L1") (pin "2") (pinfunction "2_2") (pintype "passive"))
    )
    (net (code "61") (name "Net-(D7-Pad2)") (class "Default")
      (node (ref "D7") (pin "2") (pinfunction "2_2") (pintype "bidirectional"))
      (node (ref "J2") (pin "1") (pinfunction "1_1") (pintype "bidirectional"))
      (node (ref "L4") (pin "2") (pinfunction "2_2") (pintype "passive"))
    )
    (net (code "62") (name "Net-(P1-P$1)") (class "Default")
      (node (ref "P1") (pin "1") (pinfunction "P$1_1") (pintype "bidirectional"))
      (node (ref "R11") (pin "1") (pinfunction "1_1") (pintype "passive"))
    )
    (net (code "63") (name "Net-(PWR-Pad-)") (class "Default")
      (node (ref "PWR") (pin "-") (pinfunction "-_-") (pintype "passive"))
      (node (ref "R1") (pin "2") (pinfunction "2_2") (pintype "passive"))
    )
    (net (code "64") (name "Net-(Q1-B)") (class "Default")
      (node (ref "Q1") (pin "1") (pinfunction "B_1") (pintype "passive"))
      (node (ref "R2") (pin "1") (pinfunction "1_1") (pintype "passive"))
      (node (ref "R3") (pin "2") (pinfunction "2_2") (pintype "passive"))
    )
    (net (code "65") (name "Net-(Q3-B)") (class "Default")
      (node (ref "Q3") (pin "1") (pinfunction "B_1") (pintype "passive"))
      (node (ref "R13") (pin "2") (pinfunction "2_2") (pintype "passive"))
      (node (ref "R15") (pin "1") (pinfunction "1_1") (pintype "passive"))
    )
    (net (code "66") (name "Net-(Q3-C)") (class "Default")
      (node (ref "Q3") (pin "3") (pinfunction "C_3") (pintype "passive"))
      (node (ref "R20") (pin "2") (pinfunction "2_2") (pintype "passive"))
    )
    (net (code "67") (name "Net-(Q4-B)") (class "Default")
      (node (ref "Q4") (pin "1") (pinfunction "B_1") (pintype "passive"))
      (node (ref "R14") (pin "2") (pinfunction "2_2") (pintype "passive"))
      (node (ref "R16") (pin "1") (pinfunction "1_1") (pintype "passive"))
    )
    (net (code "68") (name "Net-(Q4-C)") (class "Default")
      (node (ref "Q4") (pin "3") (pinfunction "C_3") (pintype "passive"))
      (node (ref "R21") (pin "2") (pinfunction "2_2") (pintype "passive"))
    )
    (net (code "69") (name "Net-(Q5-D)") (class "Default")
      (node (ref "D2") (pin "+") (pinfunction "+_+") (pintype "passive"))
      (node (ref "Q5") (pin "3") (pinfunction "D_3") (pintype "passive"))
      (node (ref "R23") (pin "1") (pinfunction "1_1") (pintype "passive"))
      (node (ref "T_5V") (pin "T") (pinfunction "T_T") (pintype "bidirectional"))
    )
    (net (code "70") (name "Net-(Q5-G)") (class "Default")
      (node (ref "Q5") (pin "1") (pinfunction "G_1") (pintype "passive"))
      (node (ref "R22") (pin "1") (pinfunction "1_1") (pintype "passive"))
    )
    (net (code "71") (name "Net-(SIMHOLDER-CLK)") (class "Default")
      (node (ref "R18") (pin "1") (pinfunction "1_1") (pintype "passive"))
      (node (ref "SIMHOLDER") (pin "3") (pinfunction "CLK_3") (pintype "bidirectional"))
    )
    (net (code "72") (name "Net-(SIMHOLDER-I{slash}O)") (class "Default")
      (node (ref "R19") (pin "2") (pinfunction "2_2") (pintype "passive"))
      (node (ref "SIMHOLDER") (pin "4") (pinfunction "I/O_4") (pintype "bidirectional"))
    )
    (net (code "73") (name "Net-(SIMHOLDER-RST)") (class "Default")
      (node (ref "R17") (pin "1") (pinfunction "1_1") (pintype "passive"))
      (node (ref "SIMHOLDER") (pin "2") (pinfunction "RST_2") (pintype "bidirectional"))
    )
    (net (code "74") (name "Net-(U1-EN)") (class "Default")
      (node (ref "R4") (pin "1") (pinfunction "1_1") (pintype "passive"))
      (node (ref "U1") (pin "7") (pinfunction "EN_7") (pintype "input"))
    )
    (net (code "75") (name "Net-(U1-FB)") (class "Default")
      (node (ref "C1") (pin "2") (pinfunction "2_2") (pintype "passive"))
      (node (ref "R5") (pin "1") (pinfunction "1_1") (pintype "passive"))
      (node (ref "R6") (pin "1") (pinfunction "1_1") (pintype "passive"))
      (node (ref "U1") (pin "5") (pinfunction "FB_5") (pintype "input"))
    )
    (net (code "76") (name "Net-(U1-SW)") (class "Default")
      (node (ref "D8") (pin "-") (pinfunction "-_-") (pintype "passive"))
      (node (ref "L2") (pin "1") (pinfunction "1_1") (pintype "passive"))
      (node (ref "U1") (pin "3") (pinfunction "SW_3") (pintype "output"))
    )
    (net (code "77") (name "Net-(U2-MIC_P)") (class "Default")
      (node (ref "C12") (pin "1") (pinfunction "1_1") (pintype "passive"))
      (node (ref "R12") (pin "1") (pinfunction "1_1") (pintype "passive"))
      (node (ref "U2") (pin "19") (pinfunction "MIC_P_19") (pintype "input"))
    )
    (net (code "78") (name "Net-(U2-NETLIGHT)") (class "Default")
      (node (ref "R13") (pin "1") (pinfunction "1_1") (pintype "passive"))
      (node (ref "U2") (pin "52") (pinfunction "NETLIGHT_52") (pintype "output"))
    )
    (net (code "79") (name "Net-(U2-PWRKEY_OUT)") (class "Default")
      (node (ref "POWER") (pin "1") (pinfunction "1_1") (pintype "bidirectional"))
      (node (ref "U2") (pin "2") (pinfunction "PWRKEY_OUT_2") (pintype "output"))
    )
    (net (code "80") (name "Net-(U2-RF_ANT)") (class "Default")
      (node (ref "C10") (pin "2") (pinfunction "2_2") (pintype "passive"))
      (node (ref "R10") (pin "2") (pinfunction "2_2") (pintype "passive"))
      (node (ref "U2") (pin "60") (pinfunction "RF_ANT_60") (pintype "bidirectional"))
    )
    (net (code "81") (name "Net-(U2-SPK_N)") (class "Default")
      (node (ref "C14") (pin "1") (pinfunction "1_1") (pintype "passive"))
      (node (ref "C15") (pin "2") (pinfunction "2_2") (pintype "passive"))
      (node (ref "C18") (pin "1") (pinfunction "1_1") (pintype "passive"))
      (node (ref "C19") (pin "2") (pinfunction "2_2") (pintype "passive"))
      (node (ref "L1") (pin "1") (pinfunction "1_1") (pintype "passive"))
      (node (ref "U2") (pin "22") (pinfunction "SPK_N_22") (pintype "output"))
    )
    (net (code "82") (name "Net-(U2-SPK_P)") (class "Default")
      (node (ref "C13") (pin "1") (pinfunction "1_1") (pintype "passive"))
      (node (ref "C14") (pin "2") (pinfunction "2_2") (pintype "passive"))
      (node (ref "C17") (pin "1") (pinfunction "1_1") (pintype "passive"))
      (node (ref "C18") (pin "2") (pinfunction "2_2") (pintype "passive"))
      (node (ref "L3") (pin "1") (pinfunction "1_1") (pintype "passive"))
      (node (ref "U2") (pin "21") (pinfunction "SPK_P_21") (pintype "output"))
    )
    (net (code "83") (name "Net-(U2-STATUS)") (class "Default")
      (node (ref "R14") (pin "1") (pinfunction "1_1") (pintype "passive"))
      (node (ref "U2") (pin "66") (pinfunction "STATUS_66") (pintype "output"))
    )
    (net (code "84") (name "unconnected-(J2-Pad5)") (class "Default")
      (node (ref "J2") (pin "5") (pinfunction "5_5") (pintype "bidirectional"))
    )
    (net (code "85") (name "unconnected-(J2-Pad6)") (class "Default")
      (node (ref "J2") (pin "6") (pinfunction "6_6") (pintype "bidirectional"))
    )
    (net (code "86") (name "unconnected-(J2-Pad7)") (class "Default")
      (node (ref "J2") (pin "7") (pinfunction "7_7") (pintype "bidirectional"))
    )
    (net (code "87") (name "unconnected-(J2-Pad8)") (class "Default")
      (node (ref "J2") (pin "8") (pinfunction "8_8") (pintype "bidirectional"))
    )
    (net (code "88") (name "unconnected-(SIMHOLDER-VPP-Pad5)") (class "Default")
      (node (ref "SIMHOLDER") (pin "5") (pinfunction "VPP_5") (pintype "bidirectional"))
    )
    (net (code "89") (name "unconnected-(U1-NC-Pad1)") (class "Default")
      (node (ref "U1") (pin "1") (pinfunction "NC_1") (pintype "no_connect"))
    )
    (net (code "90") (name "unconnected-(U1-NC-Pad6)") (class "Default")
      (node (ref "U1") (pin "6") (pinfunction "NC_6") (pintype "no_connect"))
    )
    (net (code "91") (name "unconnected-(U1-NC-Pad8)") (class "Default")
      (node (ref "U1") (pin "8") (pinfunction "NC_8") (pintype "no_connect"))
    )
    (net (code "92") (name "unconnected-(U2-NRESET-Pad16)") (class "Default")
      (node (ref "U2") (pin "16") (pinfunction "NRESET_16") (pintype "input"))
    )
    (net (code "93") (name "unconnected-(U2-SCL-Pad38)") (class "Default")
      (node (ref "U2") (pin "38") (pinfunction "SCL_38") (pintype "output"))
    )
    (net (code "94") (name "unconnected-(U2-SDA-Pad37)") (class "Default")
      (node (ref "U2") (pin "37") (pinfunction "SDA_37") (pintype "bidirectional"))
    )
    (net (code "95") (name "unconnected-(U2-SIM_PRESENCE-Pad34)") (class "Default")
      (node (ref "U2") (pin "34") (pinfunction "SIM_PRESENCE_34") (pintype "input"))
    )
    (net (code "96") (name "unconnected-(U3-AREF-Pad16)") (class "Default")
      (node (ref "U3") (pin "16") (pinfunction "AREF_16") (pintype "bidirectional"))
    )
    (net (code "97") (name "unconnected-(U3-GND-Pad33)") (class "Default")
      (node (ref "U3") (pin "33") (pinfunction "GND_33") (pintype "bidirectional"))
    )
    (net (code "98") (name "unconnected-(U3-MISO-Pad36)") (class "Default")
      (node (ref "U3") (pin "36") (pinfunction "MISO_36") (pintype "bidirectional"))
    )
    (net (code "99") (name "unconnected-(U3-MOSI-Pad32)") (class "Default")
      (node (ref "U3") (pin "32") (pinfunction "MOSI_32") (pintype "bidirectional"))
    )
    (net (code "100") (name "unconnected-(U3-PB2{slash}D10{slash}SS{slash}PWM-Pad11)") (class "Default")
      (node (ref "U3") (pin "11") (pinfunction "PB2/D10/SS/PWM_11") (pintype "bidirectional"))
    )
    (net (code "101") (name "unconnected-(U3-PB3{slash}D11{slash}MOSI{slash}PWM-Pad12)") (class "Default")
      (node (ref "U3") (pin "12") (pinfunction "PB3/D11/MOSI/PWM_12") (pintype "bidirectional"))
    )
    (net (code "102") (name "unconnected-(U3-PB4{slash}D12{slash}MISO-Pad13)") (class "Default")
      (node (ref "U3") (pin "13") (pinfunction "PB4/D12/MISO_13") (pintype "bidirectional"))
    )
    (net (code "103") (name "unconnected-(U3-PB5{slash}D13{slash}SCK-Pad14)") (class "Default")
      (node (ref "U3") (pin "14") (pinfunction "PB5/D13/SCK_14") (pintype "bidirectional"))
    )
    (net (code "104") (name "unconnected-(U3-PC0{slash}AD0{slash}D14-Pad17)") (class "Default")
      (node (ref "U3") (pin "17") (pinfunction "PC0/AD0/D14_17") (pintype "bidirectional"))
    )
    (net (code "105") (name "unconnected-(U3-PC1{slash}AD1{slash}D15-Pad18)") (class "Default")
      (node (ref "U3") (pin "18") (pinfunction "PC1/AD1/D15_18") (pintype "bidirectional"))
    )
    (net (code "106") (name "unconnected-(U3-PC2{slash}AD2{slash}D16-Pad19)") (class "Default")
      (node (ref "U3") (pin "19") (pinfunction "PC2/AD2/D16_19") (pintype "bidirectional"))
    )
    (net (code "107") (name "unconnected-(U3-PC3{slash}AD3{slash}D17-Pad20)") (class "Default")
      (node (ref "U3") (pin "20") (pinfunction "PC3/AD3/D17_20") (pintype "bidirectional"))
    )
    (net (code "108") (name "unconnected-(U3-PC4{slash}AD4{slash}D18{slash}SDA-Pad21)") (class "Default")
      (node (ref "U3") (pin "21") (pinfunction "PC4/AD4/D18/SDA_21") (pintype "bidirectional"))
    )
    (net (code "109") (name "unconnected-(U3-PC5{slash}AD5{slash}D19{slash}SCL-Pad22)") (class "Default")
      (node (ref "U3") (pin "22") (pinfunction "PC5/AD5/D19/SCL_22") (pintype "bidirectional"))
    )
    (net (code "110") (name "unconnected-(U3-PD2{slash}D2{slash}INT0-Pad3)") (class "Default")
      (node (ref "U3") (pin "3") (pinfunction "PD2/D2/INT0_3") (pintype "bidirectional"))
    )
    (net (code "111") (name "unconnected-(U3-PD3{slash}D3{slash}INT1{slash}PWM-Pad4)") (class "Default")
      (node (ref "U3") (pin "4") (pinfunction "PD3/D3/INT1/PWM_4") (pintype "bidirectional"))
    )
    (net (code "112") (name "unconnected-(U3-PD4{slash}D4-Pad5)") (class "Default")
      (node (ref "U3") (pin "5") (pinfunction "PD4/D4_5") (pintype "bidirectional"))
    )
    (net (code "113") (name "unconnected-(U3-PD5{slash}D5{slash}PWM-Pad6)") (class "Default")
      (node (ref "U3") (pin "6") (pinfunction "PD5/D5/PWM_6") (pintype "bidirectional"))
    )
    (net (code "114") (name "unconnected-(U3-PD6{slash}D6{slash}PWM-Pad7)") (class "Default")
      (node (ref "U3") (pin "7") (pinfunction "PD6/D6/PWM_7") (pintype "bidirectional"))
    )
    (net (code "115") (name "unconnected-(U3-RESET-Pad28)") (class "Default")
      (node (ref "U3") (pin "28") (pinfunction "RESET_28") (pintype "bidirectional"))
    )
    (net (code "116") (name "unconnected-(U3-RST-Pad34)") (class "Default")
      (node (ref "U3") (pin "34") (pinfunction "RST_34") (pintype "bidirectional"))
    )
    (net (code "117") (name "unconnected-(U3-SCK-Pad35)") (class "Default")
      (node (ref "U3") (pin "35") (pinfunction "SCK_35") (pintype "bidirectional"))
    )
    (net (code "118") (name "unconnected-(U3-VCC-Pad31)") (class "Default")
      (node (ref "U3") (pin "31") (pinfunction "VCC_31") (pintype "bidirectional"))
    )
  )
)
